# Temp_Sensirion_assy_FPC.net
KiCad netlist of a schematic drawn in Altium Designer
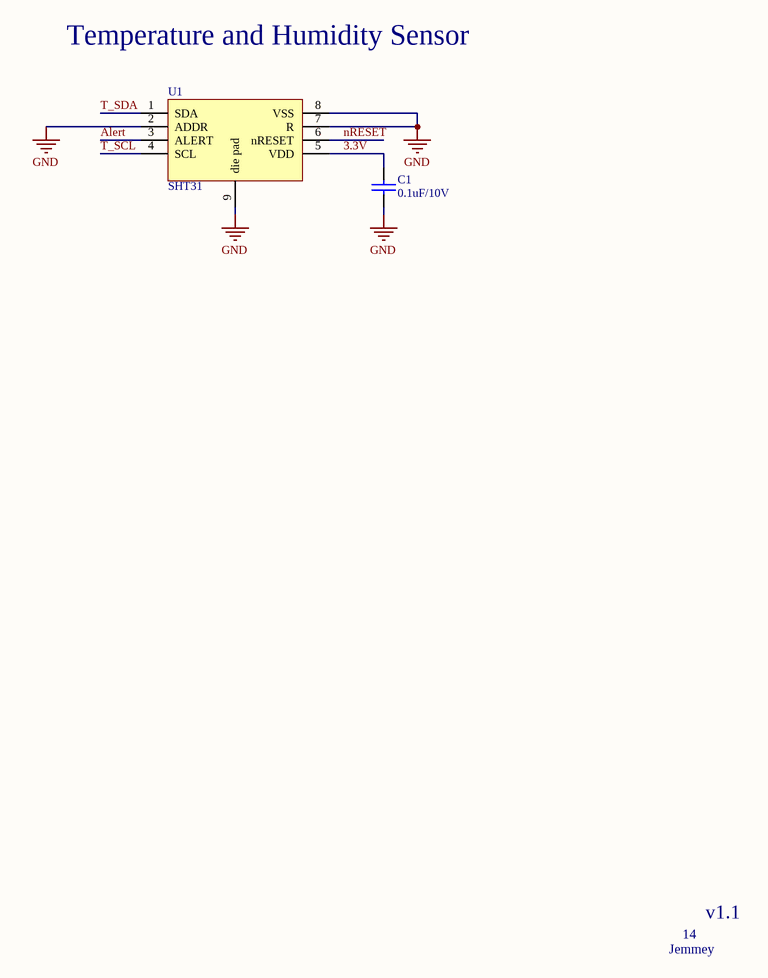
[diagram p0: Temp Sensirion assy FPC.SchDoc]

(export (version "E")
  (design (tool "Eeschema 10.0.6"))
  (components
    (comp (ref "C1")
      (value "0.1uF/10V")
      (footprint "0402C")
      (description "厂家：Murata，型号：GRM155R71A104KA01D")
      (libsource (lib "*") (part "CAP"))
    )
    (comp (ref "U1")
      (value "SHT31")
      (footprint "DFN")
      (description "厂家：盛思睿，型号：SHT31")
      (libsource (lib "Temp Sensirion assy FPC") (part "SHT31"))
    )
  )
  (nets
    (net (code "1") (name "/3.3V") (class "Default")
      (node (ref "C1") (pin "1") (pinfunction "1_1") (pintype "passive"))
      (node (ref "U1") (pin "5") (pinfunction "VDD_5") (pintype "passive"))
    )
    (net (code "2") (name "/Alert") (class "Default")
      (node (ref "U1") (pin "3") (pinfunction "ALERT_3") (pintype "passive"))
    )
    (net (code "3") (name "/T_SCL") (class "Default")
      (node (ref "U1") (pin "4") (pinfunction "SCL_4") (pintype "passive"))
    )
    (net (code "4") (name "/T_SDA") (class "Default")
      (node (ref "U1") (pin "1") (pinfunction "SDA_1") (pintype "passive"))
    )
    (net (code "5") (name "/nRESET") (class "Default")
      (node (ref "U1") (pin "6") (pinfunction "nRESET_6") (pintype "passive"))
    )
    (net (code "6") (name "GND") (class "Default")
      (node (ref "C1") (pin "2") (pinfunction "2_2") (pintype "passive"))
      (node (ref "U1") (pin "2") (pinfunction "ADDR_2") (pintype "passive"))
      (node (ref "U1") (pin "7") (pinfunction "R_7") (pintype "passive"))
      (node (ref "U1") (pin "8") (pinfunction "VSS_8") (pintype "passive"))
      (node (ref "U1") (pin "9") (pinfunction "die_pad_9") (pintype "passive"))
    )
  )
)
